# ESP_Uart-V2.net
KiCad netlist of a schematic drawn in EAGLE
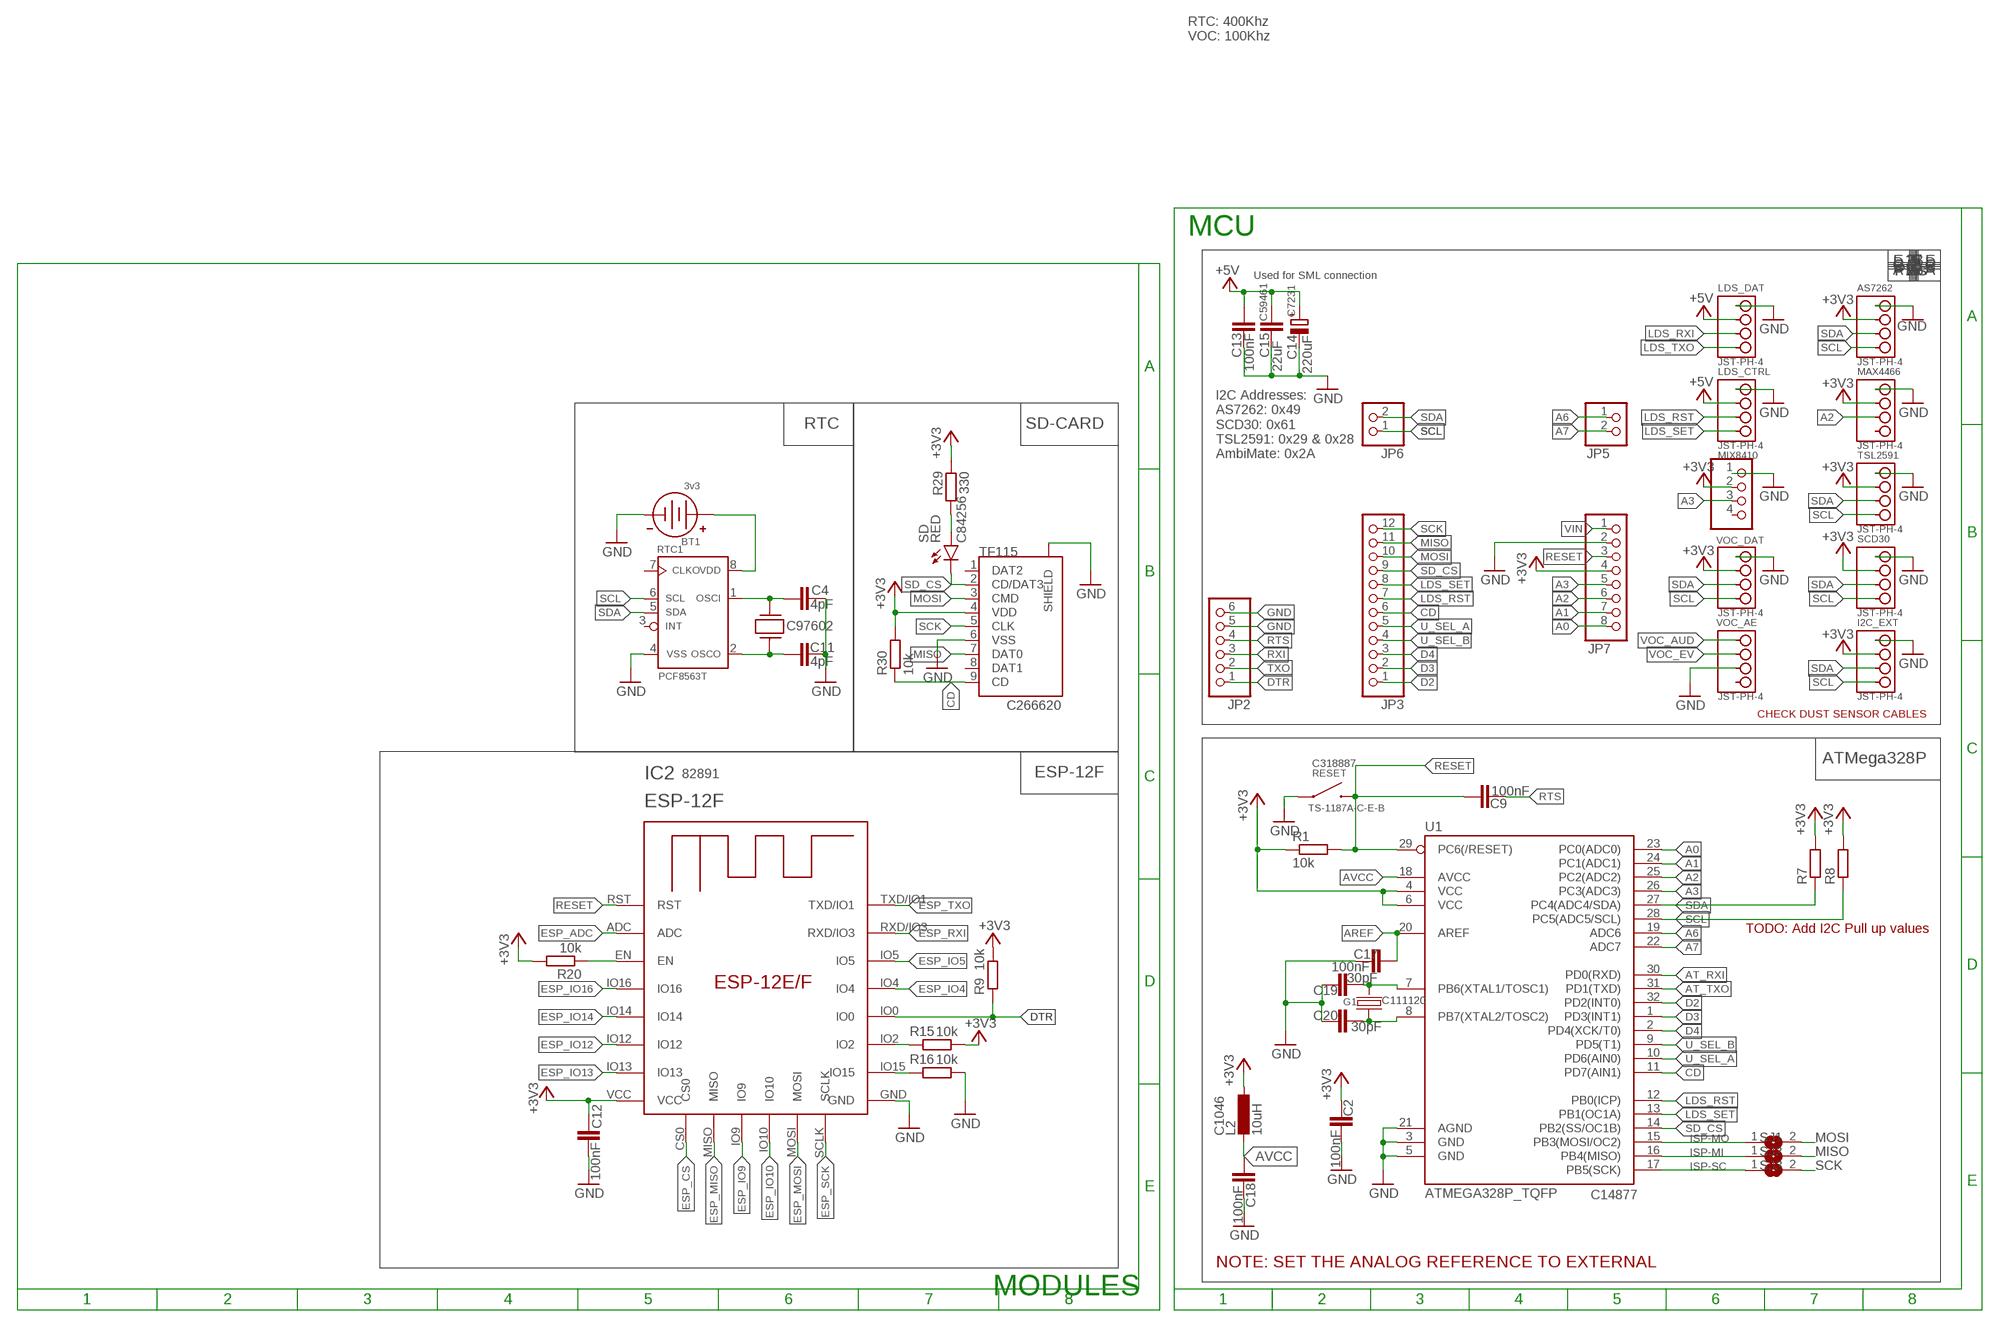
[diagram p0: schematic, sheet 1, part 1 of 2]
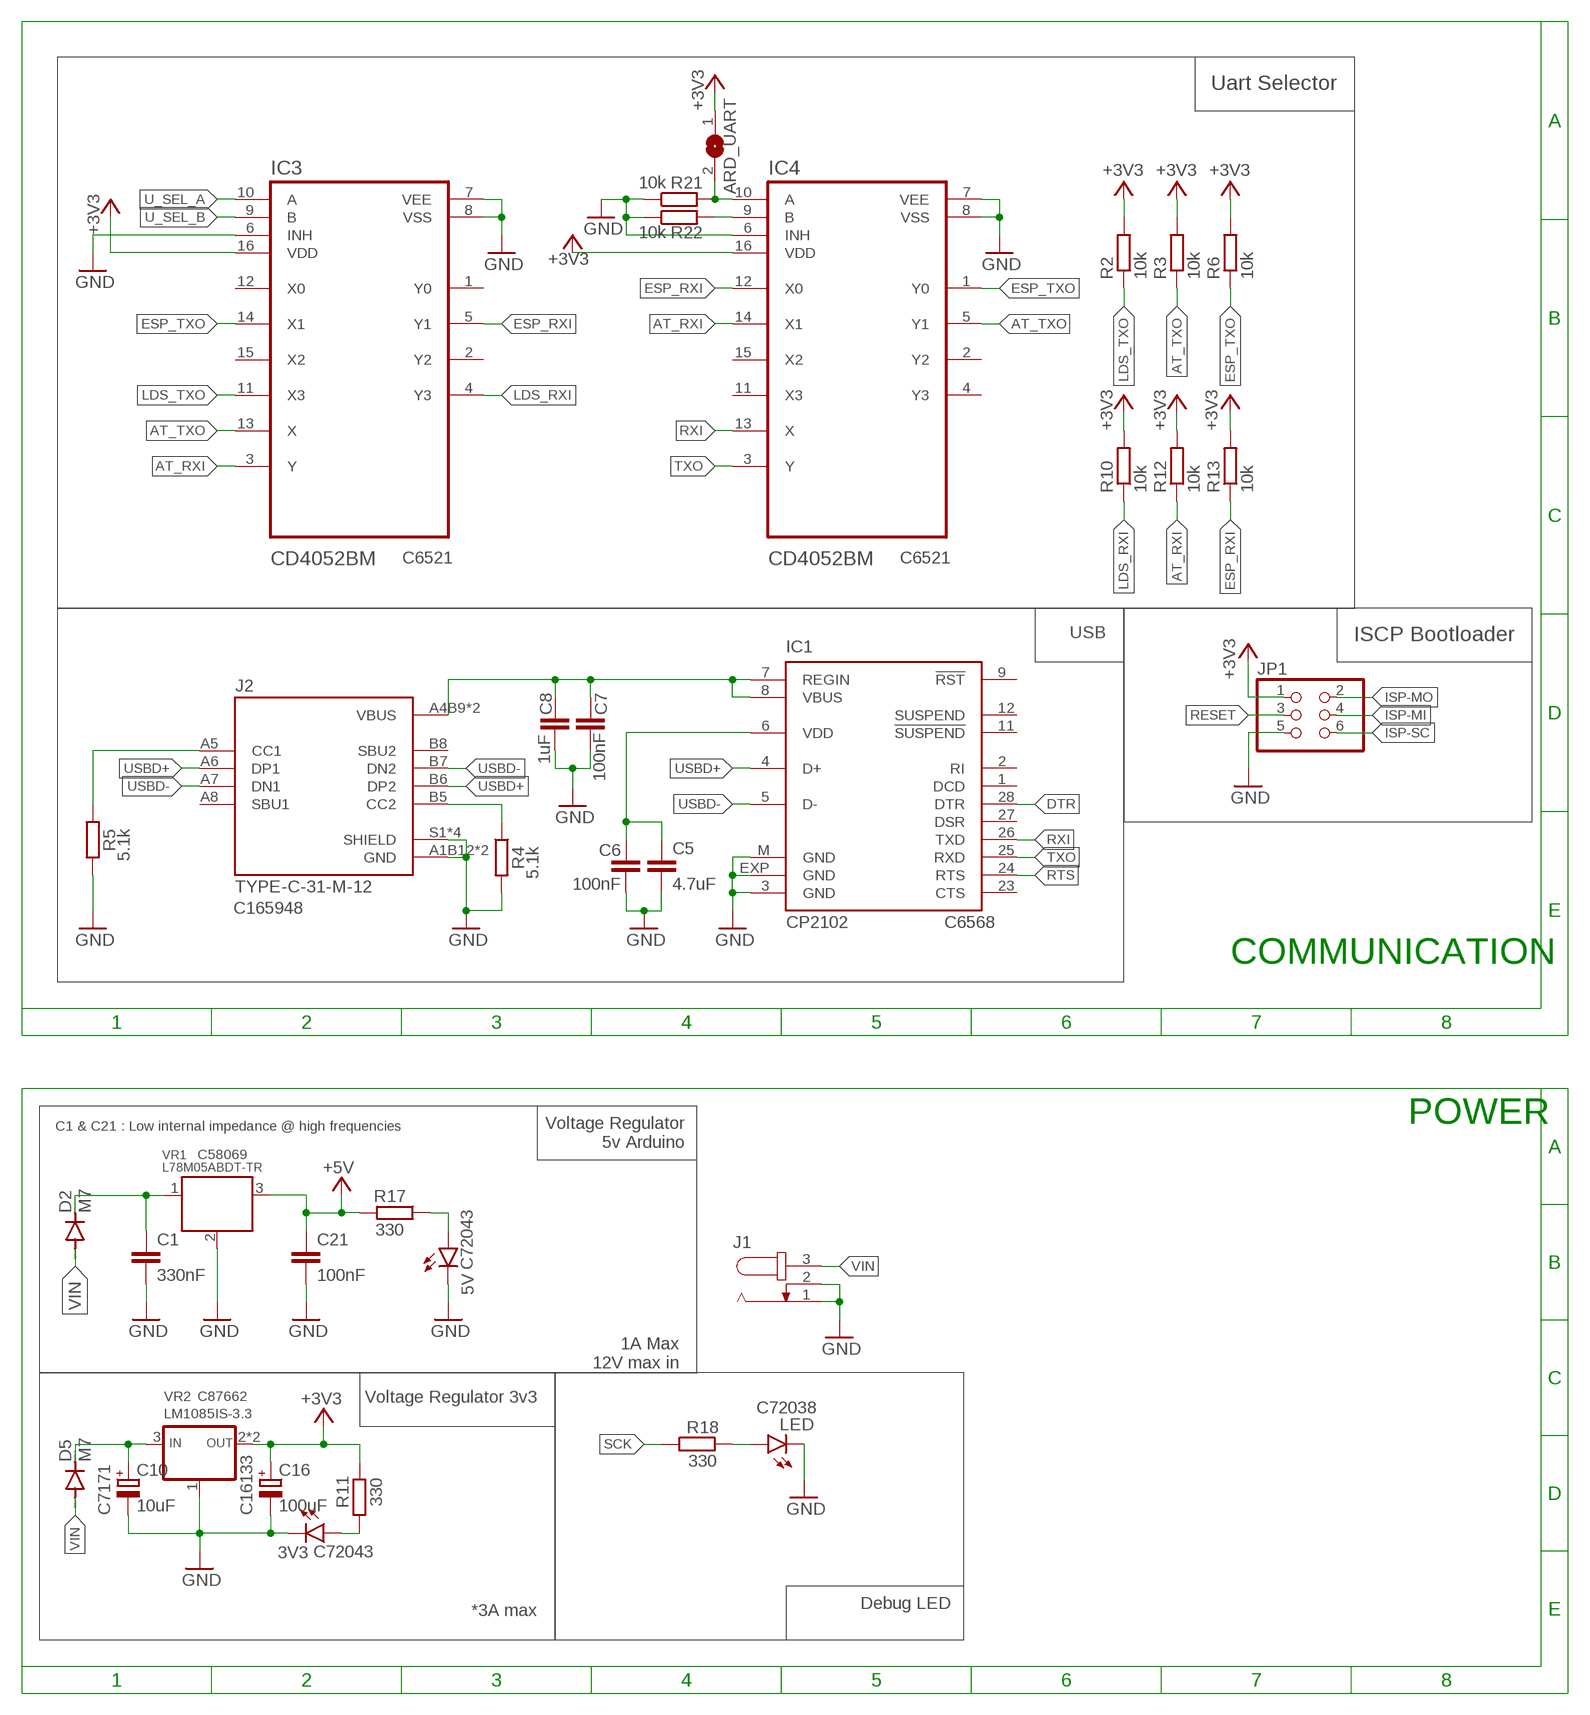
[diagram p1: schematic, sheet 1, part 2 of 2]

(export (version "E")
  (design (tool "Eeschema 10.0.6"))
  (components
    (comp (ref "3V3")
      (value "C72043")
      (footprint "eagle-import:CHIPLED_0603")
      (fields (field (name "PTNR") "C72043"))
      (libsource (lib "eagle-import") (part "LEDCHIPLED_0603"))
    )
    (comp (ref "5V")
      (value "C72043")
      (footprint "eagle-import:CHIPLED_0603")
      (fields (field (name "PTNR") "C72043"))
      (libsource (lib "eagle-import") (part "LEDCHIPLED_0603"))
    )
    (comp (ref "ARD_UART")
      (value "SJ")
      (footprint "eagle-import:SJ")
      (libsource (lib "eagle-import") (part "SJ"))
    )
    (comp (ref "AS7262")
      (value "JST-PH-4")
      (footprint "eagle-import:JST-PH-4")
      (libsource (lib "eagle-import") (part "JST-PH-4"))
    )
    (comp (ref "BT1")
      (value "3v3")
      (footprint "eagle-import:CH29-2032LF")
      (libsource (lib "eagle-import") (part "CH29-2032LF"))
    )
    (comp (ref "C1")
      (value "330nF")
      (footprint "eagle-import:C0805")
      (libsource (lib "eagle-import") (part "C-EUC0805"))
    )
    (comp (ref "C2")
      (value "100nF")
      (footprint "eagle-import:C0402")
      (libsource (lib "eagle-import") (part "C-EUC0402"))
    )
    (comp (ref "C4")
      (value "4pF")
      (footprint "eagle-import:C0402")
      (libsource (lib "eagle-import") (part "C-EUC0402"))
    )
    (comp (ref "C5")
      (value "4.7uF")
      (footprint "eagle-import:C0402")
      (libsource (lib "eagle-import") (part "C-EUC0402"))
    )
    (comp (ref "C6")
      (value "100nF")
      (footprint "eagle-import:C0402")
      (libsource (lib "eagle-import") (part "C-EUC0402"))
    )
    (comp (ref "C7")
      (value "100nF")
      (footprint "eagle-import:C0402")
      (libsource (lib "eagle-import") (part "C-EUC0402"))
    )
    (comp (ref "C8")
      (value "1uF")
      (footprint "eagle-import:C0402")
      (libsource (lib "eagle-import") (part "C-EUC0402"))
    )
    (comp (ref "C9")
      (value "100nF")
      (footprint "eagle-import:C0402")
      (libsource (lib "eagle-import") (part "C-EUC0402"))
    )
    (comp (ref "C10")
      (value "10uF")
      (footprint "eagle-import:A_3216-18R")
      (fields (field (name "PTRNR") "C7171"))
      (libsource (lib "eagle-import") (part "CPOL-EUA/3216-18R"))
    )
    (comp (ref "C11")
      (value "4pF")
      (footprint "eagle-import:C0402")
      (libsource (lib "eagle-import") (part "C-EUC0402"))
    )
    (comp (ref "C12")
      (value "100nF")
      (footprint "eagle-import:C0402")
      (libsource (lib "eagle-import") (part "C-EUC0402"))
    )
    (comp (ref "C13")
      (value "100nF")
      (footprint "eagle-import:C0402")
      (libsource (lib "eagle-import") (part "C-EUC0402"))
    )
    (comp (ref "C14")
      (value "220uF")
      (footprint "eagle-import:A_3216-18R")
      (fields (field (name "PTRNR") "C7231"))
      (libsource (lib "eagle-import") (part "CPOL-EUA/3216-18R"))
    )
    (comp (ref "C15")
      (value "22uF")
      (footprint "eagle-import:C0603")
      (fields (field (name "PTRNR") "C59461"))
      (libsource (lib "eagle-import") (part "C-EUC0603"))
    )
    (comp (ref "C16")
      (value "100uF")
      (footprint "eagle-import:B_3528-21W")
      (fields (field (name "PTRNR") "C16133"))
      (libsource (lib "eagle-import") (part "CPOL-EUB/3528-21W"))
    )
    (comp (ref "C17")
      (value "100nF")
      (footprint "eagle-import:C0402")
      (libsource (lib "eagle-import") (part "C-EUC0402"))
    )
    (comp (ref "C18")
      (value "100nF")
      (footprint "eagle-import:C0402")
      (libsource (lib "eagle-import") (part "C-EUC0402"))
    )
    (comp (ref "C19")
      (value "30pF")
      (footprint "eagle-import:C0402")
      (libsource (lib "eagle-import") (part "C-EUC0402"))
    )
    (comp (ref "C20")
      (value "30pF")
      (footprint "eagle-import:C0402")
      (libsource (lib "eagle-import") (part "C-EUC0402"))
    )
    (comp (ref "C21")
      (value "100nF")
      (footprint "eagle-import:C0402")
      (libsource (lib "eagle-import") (part "C-EUC0402"))
    )
    (comp (ref "D2")
      (value "M7")
      (footprint "eagle-import:DO-214AC")
      (libsource (lib "eagle-import") (part "M7DO-214AC"))
    )
    (comp (ref "D5")
      (value "M7")
      (footprint "eagle-import:DO-214AC")
      (libsource (lib "eagle-import") (part "M7DO-214AC"))
    )
    (comp (ref "G1")
      (value "8Mhz")
      (footprint "eagle-import:7A08000008")
      (fields (field (name "PTRNR") "C111120"))
      (libsource (lib "eagle-import") (part "7A08000008"))
    )
    (comp (ref "G2")
      (value "32.768KHZ")
      (footprint "eagle-import:32.768KHZ")
      (fields (field (name "PTRNR") "C97602"))
      (libsource (lib "eagle-import") (part "32.768KHZ"))
    )
    (comp (ref "I2C_EXT")
      (value "JST-PH-4")
      (footprint "eagle-import:JST-PH-4")
      (libsource (lib "eagle-import") (part "JST-PH-4"))
    )
    (comp (ref "IC1")
      (value "CP2102")
      (footprint "eagle-import:MLP28")
      (fields
        (field (name "MF") "FARNELL")
        (field (name "MPN") "CP2102-GM")
        (field (name "PTRNR") "C6568")
        (field (name "PTRNR_1") "C6568")
      )
      (libsource (lib "eagle-import") (part "CP2102"))
    )
    (comp (ref "IC2")
      (value "ESP-12F")
      (footprint "eagle-import:ESP-12E")
      (fields (field (name "PTRNR") "82891"))
      (libsource (lib "eagle-import") (part "ESP-12F"))
    )
    (comp (ref "IC3")
      (value "CD4052BM")
      (footprint "eagle-import:SOIC127P600X175-16N")
      (fields
        (field (name "MF") "Texas Instruments")
        (field (name "PTRNR") "C6521")
        (field (name "PTRNR_1") "C6521")
      )
      (libsource (lib "eagle-import") (part "CD4052BM"))
    )
    (comp (ref "IC4")
      (value "CD4052BM")
      (footprint "eagle-import:SOIC127P600X175-16N")
      (fields
        (field (name "MF") "Texas Instruments")
        (field (name "PTRNR") "C6521")
        (field (name "PTRNR_1") "C6521")
      )
      (libsource (lib "eagle-import") (part "CD4052BM"))
    )
    (comp (ref "J1")
      (value "JACK-PLUG1")
      (footprint "eagle-import:SPC4078")
      (libsource (lib "eagle-import") (part "JACK-PLUG1"))
    )
    (comp (ref "J2")
      (value "TYPE-C-31-M-12")
      (footprint "eagle-import:HRO_TYPE-C-31-M-12")
      (fields
        (field (name "MF") "HRO Electronics Co., Ltd.")
        (field (name "PTRNR") "C165948")
        (field (name "PTRNR_1") "C165948")
      )
      (libsource (lib "eagle-import") (part "TYPE-C-31-M-12"))
    )
    (comp (ref "JP1")
      (value "PINHD-2X3")
      (footprint "eagle-import:2X03")
      (libsource (lib "eagle-import") (part "PINHD-2X3"))
    )
    (comp (ref "JP2")
      (value "PINHD-1X6/90")
      (footprint "eagle-import:1X06_90")
      (libsource (lib "eagle-import") (part "PINHD-1X6/90"))
    )
    (comp (ref "JP3")
      (value "PINHD-1X12")
      (footprint "eagle-import:1X12")
      (libsource (lib "eagle-import") (part "PINHD-1X12"))
    )
    (comp (ref "JP5")
      (value "PINHD-1X2/90")
      (footprint "eagle-import:1X02_90")
      (libsource (lib "eagle-import") (part "PINHD-1X2/90"))
    )
    (comp (ref "JP6")
      (value "PINHD-1X2/90")
      (footprint "eagle-import:1X02_90")
      (libsource (lib "eagle-import") (part "PINHD-1X2/90"))
    )
    (comp (ref "JP7")
      (value "PINHD-1X8")
      (footprint "eagle-import:1X08")
      (libsource (lib "eagle-import") (part "PINHD-1X8"))
    )
    (comp (ref "L2")
      (value "10uH")
      (footprint "eagle-import:L2012C")
      (fields (field (name "PRTNR") "C1046"))
      (libsource (lib "eagle-import") (part "L-EUL2012C"))
    )
    (comp (ref "LDS_CTRL")
      (value "JST-PH-4")
      (footprint "eagle-import:JST-PH-4")
      (libsource (lib "eagle-import") (part "JST-PH-4"))
    )
    (comp (ref "LDS_DAT")
      (value "JST-PH-4")
      (footprint "eagle-import:JST-PH-4")
      (libsource (lib "eagle-import") (part "JST-PH-4"))
    )
    (comp (ref "LED")
      (value "YELLOW")
      (footprint "eagle-import:CHIPLED_0603")
      (fields (field (name "PTRNR") "C72038"))
      (libsource (lib "eagle-import") (part "LEDCHIPLED_0603"))
    )
    (comp (ref "MAX4466")
      (value "JST-PH-4")
      (footprint "eagle-import:JST-PH-4")
      (libsource (lib "eagle-import") (part "JST-PH-4"))
    )
    (comp (ref "MIX8410")
      (value "PINHD-1X4")
      (footprint "eagle-import:1X04")
      (libsource (lib "eagle-import") (part "PINHD-1X4"))
    )
    (comp (ref "R1")
      (value "10k")
      (footprint "eagle-import:R0402")
      (libsource (lib "eagle-import") (part "R-EU_R0402"))
    )
    (comp (ref "R2")
      (value "10k")
      (footprint "eagle-import:R0402")
      (libsource (lib "eagle-import") (part "R-EU_R0402"))
    )
    (comp (ref "R3")
      (value "10k")
      (footprint "eagle-import:R0402")
      (libsource (lib "eagle-import") (part "R-EU_R0402"))
    )
    (comp (ref "R4")
      (value "5.1k")
      (footprint "eagle-import:R0402")
      (libsource (lib "eagle-import") (part "R-EU_R0402"))
    )
    (comp (ref "R5")
      (value "5.1k")
      (footprint "eagle-import:R0402")
      (libsource (lib "eagle-import") (part "R-EU_R0402"))
    )
    (comp (ref "R6")
      (value "10k")
      (footprint "eagle-import:R0402")
      (libsource (lib "eagle-import") (part "R-EU_R0402"))
    )
    (comp (ref "R7")
      (value "R-EU_R0402")
      (footprint "eagle-import:R0402")
      (libsource (lib "eagle-import") (part "R-EU_R0402"))
    )
    (comp (ref "R8")
      (value "R-EU_R0402")
      (footprint "eagle-import:R0402")
      (libsource (lib "eagle-import") (part "R-EU_R0402"))
    )
    (comp (ref "R9")
      (value "10k")
      (footprint "eagle-import:R0402")
      (libsource (lib "eagle-import") (part "R-EU_R0402"))
    )
    (comp (ref "R10")
      (value "10k")
      (footprint "eagle-import:R0402")
      (libsource (lib "eagle-import") (part "R-EU_R0402"))
    )
    (comp (ref "R11")
      (value "330")
      (footprint "eagle-import:M0805")
      (libsource (lib "eagle-import") (part "R-EU_M0805"))
    )
    (comp (ref "R12")
      (value "10k")
      (footprint "eagle-import:R0402")
      (libsource (lib "eagle-import") (part "R-EU_R0402"))
    )
    (comp (ref "R13")
      (value "10k")
      (footprint "eagle-import:R0402")
      (libsource (lib "eagle-import") (part "R-EU_R0402"))
    )
    (comp (ref "R15")
      (value "10k")
      (footprint "eagle-import:R0402")
      (libsource (lib "eagle-import") (part "R-EU_R0402"))
    )
    (comp (ref "R16")
      (value "10k")
      (footprint "eagle-import:R0402")
      (libsource (lib "eagle-import") (part "R-EU_R0402"))
    )
    (comp (ref "R17")
      (value "330")
      (footprint "eagle-import:M0805")
      (libsource (lib "eagle-import") (part "R-EU_M0805"))
    )
    (comp (ref "R18")
      (value "330")
      (footprint "eagle-import:M0805")
      (libsource (lib "eagle-import") (part "R-EU_M0805"))
    )
    (comp (ref "R20")
      (value "10k")
      (footprint "eagle-import:R0402")
      (libsource (lib "eagle-import") (part "R-EU_R0402"))
    )
    (comp (ref "R21")
      (value "10k")
      (footprint "eagle-import:R0402")
      (libsource (lib "eagle-import") (part "R-EU_R0402"))
    )
    (comp (ref "R22")
      (value "10k")
      (footprint "eagle-import:R0402")
      (libsource (lib "eagle-import") (part "R-EU_R0402"))
    )
    (comp (ref "R29")
      (value "330")
      (footprint "eagle-import:R0402")
      (libsource (lib "eagle-import") (part "R-EU_R0402"))
    )
    (comp (ref "R30")
      (value "10k")
      (footprint "eagle-import:R0402")
      (libsource (lib "eagle-import") (part "R-EU_R0402"))
    )
    (comp (ref "RESET")
      (value "TS-1187A-C-E-B")
      (footprint "eagle-import:TS-1187A-C-E-B")
      (fields (field (name "PRTNR") "C318887") (field (name "PRTNR_1") "C318887"))
      (libsource (lib "eagle-import") (part "TS-1187A-C-E-B"))
    )
    (comp (ref "RTC1")
      (value "PCF8563T")
      (footprint "eagle-import:SOIC8")
      (libsource (lib "eagle-import") (part "PCF8563T"))
    )
    (comp (ref "SCD30")
      (value "JST-PH-4")
      (footprint "eagle-import:JST-PH-4")
      (libsource (lib "eagle-import") (part "JST-PH-4"))
    )
    (comp (ref "SD")
      (value "RED")
      (footprint "eagle-import:CHIPLED_0805")
      (fields (field (name "PTRNR") "C84256"))
      (libsource (lib "eagle-import") (part "LEDCHIPLED_0805"))
    )
    (comp (ref "SJ1") (value "SJ") (footprint "eagle-import:SJ") (libsource (lib "eagle-import") (part "SJ")))
    (comp (ref "SJ2") (value "SJ") (footprint "eagle-import:SJ") (libsource (lib "eagle-import") (part "SJ")))
    (comp (ref "SJ3") (value "SJ") (footprint "eagle-import:SJ") (libsource (lib "eagle-import") (part "SJ")))
    (comp (ref "TF115")
      (value "TF-115")
      (footprint "eagle-import:TF-115")
      (fields (field (name "PTRNR") "C266620"))
      (libsource (lib "eagle-import") (part "TF-115"))
    )
    (comp (ref "TSL2591")
      (value "JST-PH-4")
      (footprint "eagle-import:JST-PH-4")
      (libsource (lib "eagle-import") (part "JST-PH-4"))
    )
    (comp (ref "U1")
      (value "ATMEGA328P_TQFP")
      (footprint "eagle-import:TQFP32-08")
      (fields (field (name "PTRNR") "C14877"))
      (libsource (lib "eagle-import") (part "ATMEGA328P_TQFP"))
    )
    (comp (ref "VOC_AE")
      (value "JST-PH-4")
      (footprint "eagle-import:JST-PH-4")
      (libsource (lib "eagle-import") (part "JST-PH-4"))
    )
    (comp (ref "VOC_DAT")
      (value "JST-PH-4")
      (footprint "eagle-import:JST-PH-4")
      (libsource (lib "eagle-import") (part "JST-PH-4"))
    )
    (comp (ref "VR1")
      (value "L78M05ABDT-TR")
      (footprint "eagle-import:DPAK")
      (fields (field (name "PTRNR") "C58069"))
      (libsource (lib "eagle-import") (part "L78M05ABDT-TR"))
    )
    (comp (ref "VR2")
      (value "LM1085IS-3.3")
      (footprint "eagle-import:TO263-3")
      (fields (field (name "PTRNR") "C87662") (field (name "PTRNR_1") "C87662"))
      (libsource (lib "eagle-import") (part "LM1085IS-3.3"))
    )
  )
  (nets
    (net (code "1") (name "+3V3") (class "Default")
      (node (ref "ARD_UART") (pin "1") (pinfunction "1_1") (pintype "passive"))
      (node (ref "AS7262") (pin "P2") (pinfunction "2_P2") (pintype "bidirectional"))
      (node (ref "C12") (pin "1") (pinfunction "1_1") (pintype "passive"))
      (node (ref "C16") (pin "+") (pinfunction "+_+") (pintype "passive"))
      (node (ref "C2") (pin "2") (pinfunction "2_2") (pintype "passive"))
      (node (ref "I2C_EXT") (pin "P2") (pinfunction "2_P2") (pintype "bidirectional"))
      (node (ref "IC2") (pin "VCC") (pinfunction "VCC_VCC") (pintype "power_in"))
      (node (ref "IC3") (pin "16") (pinfunction "VDD_16") (pintype "input"))
      (node (ref "IC4") (pin "16") (pinfunction "VDD_16") (pintype "input"))
      (node (ref "JP1") (pin "1") (pinfunction "1_1") (pintype "passive"))
      (node (ref "JP7") (pin "4") (pinfunction "4_4") (pintype "passive"))
      (node (ref "L2") (pin "1") (pinfunction "1_1") (pintype "passive"))
      (node (ref "MAX4466") (pin "P2") (pinfunction "2_P2") (pintype "bidirectional"))
      (node (ref "MIX8410") (pin "2") (pinfunction "2_2") (pintype "passive"))
      (node (ref "R1") (pin "1") (pinfunction "1_1") (pintype "passive"))
      (node (ref "R10") (pin "2") (pinfunction "2_2") (pintype "passive"))
      (node (ref "R11") (pin "2") (pinfunction "2_2") (pintype "passive"))
      (node (ref "R12") (pin "2") (pinfunction "2_2") (pintype "passive"))
      (node (ref "R13") (pin "2") (pinfunction "2_2") (pintype "passive"))
      (node (ref "R15") (pin "1") (pinfunction "1_1") (pintype "passive"))
      (node (ref "R2") (pin "2") (pinfunction "2_2") (pintype "passive"))
      (node (ref "R20") (pin "2") (pinfunction "2_2") (pintype "passive"))
      (node (ref "R29") (pin "2") (pinfunction "2_2") (pintype "passive"))
      (node (ref "R3") (pin "2") (pinfunction "2_2") (pintype "passive"))
      (node (ref "R30") (pin "2") (pinfunction "2_2") (pintype "passive"))
      (node (ref "R6") (pin "2") (pinfunction "2_2") (pintype "passive"))
      (node (ref "R7") (pin "2") (pinfunction "2_2") (pintype "passive"))
      (node (ref "R8") (pin "2") (pinfunction "2_2") (pintype "passive"))
      (node (ref "R9") (pin "1") (pinfunction "1_1") (pintype "passive"))
      (node (ref "SCD30") (pin "P2") (pinfunction "2_P2") (pintype "bidirectional"))
      (node (ref "TF115") (pin "4") (pinfunction "VDD_4") (pintype "bidirectional"))
      (node (ref "TSL2591") (pin "P2") (pinfunction "2_P2") (pintype "bidirectional"))
      (node (ref "U1") (pin "4") (pinfunction "VCC_4") (pintype "bidirectional"))
      (node (ref "U1") (pin "6") (pinfunction "VCC_6") (pintype "bidirectional"))
      (node (ref "VOC_DAT") (pin "P2") (pinfunction "2_P2") (pintype "bidirectional"))
      (node (ref "VR2") (pin "2") (pinfunction "OUT_2") (pintype "output"))
      (node (ref "VR2") (pin "TAB") (pinfunction "OUT_TAB") (pintype "output"))
    )
    (net (code "2") (name "+5V") (class "Default")
      (node (ref "C13") (pin "1") (pinfunction "1_1") (pintype "passive"))
      (node (ref "C14") (pin "+") (pinfunction "+_+") (pintype "passive"))
      (node (ref "C15") (pin "1") (pinfunction "1_1") (pintype "passive"))
      (node (ref "C21") (pin "1") (pinfunction "1_1") (pintype "passive"))
      (node (ref "LDS_CTRL") (pin "P2") (pinfunction "2_P2") (pintype "bidirectional"))
      (node (ref "LDS_DAT") (pin "P2") (pinfunction "2_P2") (pintype "bidirectional"))
      (node (ref "R17") (pin "2") (pinfunction "2_2") (pintype "passive"))
      (node (ref "VR1") (pin "3") (pinfunction "VO_3") (pintype "output"))
    )
    (net (code "3") (name "A0") (class "Default")
      (node (ref "JP7") (pin "8") (pinfunction "8_8") (pintype "passive"))
      (node (ref "U1") (pin "23") (pinfunction "PC0(ADC0)_23") (pintype "bidirectional"))
    )
    (net (code "4") (name "A1") (class "Default")
      (node (ref "JP7") (pin "7") (pinfunction "7_7") (pintype "passive"))
      (node (ref "U1") (pin "24") (pinfunction "PC1(ADC1)_24") (pintype "bidirectional"))
    )
    (net (code "5") (name "A2") (class "Default")
      (node (ref "JP7") (pin "6") (pinfunction "6_6") (pintype "passive"))
      (node (ref "MAX4466") (pin "P3") (pinfunction "3_P3") (pintype "bidirectional"))
      (node (ref "U1") (pin "25") (pinfunction "PC2(ADC2)_25") (pintype "bidirectional"))
    )
    (net (code "6") (name "A3") (class "Default")
      (node (ref "JP7") (pin "5") (pinfunction "5_5") (pintype "passive"))
      (node (ref "MIX8410") (pin "3") (pinfunction "3_3") (pintype "passive"))
      (node (ref "U1") (pin "26") (pinfunction "PC3(ADC3)_26") (pintype "bidirectional"))
    )
    (net (code "7") (name "A6") (class "Default")
      (node (ref "JP5") (pin "1") (pinfunction "1_1") (pintype "passive"))
      (node (ref "U1") (pin "19") (pinfunction "ADC6_19") (pintype "bidirectional"))
    )
    (net (code "8") (name "A7") (class "Default")
      (node (ref "JP5") (pin "2") (pinfunction "2_2") (pintype "passive"))
      (node (ref "U1") (pin "22") (pinfunction "ADC7_22") (pintype "bidirectional"))
    )
    (net (code "9") (name "AREF") (class "Default")
      (node (ref "C17") (pin "1") (pinfunction "1_1") (pintype "passive"))
      (node (ref "U1") (pin "20") (pinfunction "AREF_20") (pintype "bidirectional"))
    )
    (net (code "10") (name "AT_RXI") (class "Default")
      (node (ref "IC3") (pin "3") (pinfunction "Y_3") (pintype "bidirectional"))
      (node (ref "IC4") (pin "14") (pinfunction "X1_14") (pintype "bidirectional"))
      (node (ref "R12") (pin "1") (pinfunction "1_1") (pintype "passive"))
      (node (ref "U1") (pin "30") (pinfunction "PD0(RXD)_30") (pintype "bidirectional"))
    )
    (net (code "11") (name "AT_TXO") (class "Default")
      (node (ref "IC3") (pin "13") (pinfunction "X_13") (pintype "bidirectional"))
      (node (ref "IC4") (pin "5") (pinfunction "Y1_5") (pintype "bidirectional"))
      (node (ref "R3") (pin "1") (pinfunction "1_1") (pintype "passive"))
      (node (ref "U1") (pin "31") (pinfunction "PD1(TXD)_31") (pintype "bidirectional"))
    )
    (net (code "12") (name "AVCC") (class "Default")
      (node (ref "C18") (pin "2") (pinfunction "2_2") (pintype "passive"))
      (node (ref "L2") (pin "2") (pinfunction "2_2") (pintype "passive"))
      (node (ref "U1") (pin "18") (pinfunction "AVCC_18") (pintype "bidirectional"))
    )
    (net (code "13") (name "CD") (class "Default")
      (node (ref "JP3") (pin "6") (pinfunction "6_6") (pintype "passive"))
      (node (ref "R30") (pin "1") (pinfunction "1_1") (pintype "passive"))
      (node (ref "TF115") (pin "9") (pinfunction "CD_9") (pintype "bidirectional"))
      (node (ref "U1") (pin "11") (pinfunction "PD7(AIN1)_11") (pintype "bidirectional"))
    )
    (net (code "14") (name "D2") (class "Default")
      (node (ref "JP3") (pin "1") (pinfunction "1_1") (pintype "passive"))
      (node (ref "U1") (pin "32") (pinfunction "PD2(INT0)_32") (pintype "bidirectional"))
    )
    (net (code "15") (name "D3") (class "Default")
      (node (ref "JP3") (pin "2") (pinfunction "2_2") (pintype "passive"))
      (node (ref "U1") (pin "1") (pinfunction "PD3(INT1)_1") (pintype "bidirectional"))
    )
    (net (code "16") (name "D4") (class "Default")
      (node (ref "JP3") (pin "3") (pinfunction "3_3") (pintype "passive"))
      (node (ref "U1") (pin "2") (pinfunction "PD4(XCK/T0)_2") (pintype "bidirectional"))
    )
    (net (code "17") (name "DTR") (class "Default")
      (node (ref "IC1") (pin "28") (pinfunction "DTR_28") (pintype "output"))
      (node (ref "IC2") (pin "IO0") (pinfunction "IO0_IO0") (pintype "bidirectional"))
      (node (ref "JP2") (pin "1") (pinfunction "1_1") (pintype "passive"))
      (node (ref "R9") (pin "2") (pinfunction "2_2") (pintype "passive"))
    )
    (net (code "18") (name "ESP_ADC") (class "Default")
      (node (ref "IC2") (pin "ADC") (pinfunction "ADC_ADC") (pintype "bidirectional"))
    )
    (net (code "19") (name "ESP_CS") (class "Default")
      (node (ref "IC2") (pin "CS0") (pinfunction "CS0_CS0") (pintype "bidirectional"))
    )
    (net (code "20") (name "ESP_IO4") (class "Default")
      (node (ref "IC2") (pin "IO4") (pinfunction "IO4_IO4") (pintype "bidirectional"))
    )
    (net (code "21") (name "ESP_IO5") (class "Default")
      (node (ref "IC2") (pin "IO5") (pinfunction "IO5_IO5") (pintype "bidirectional"))
    )
    (net (code "22") (name "ESP_IO9") (class "Default")
      (node (ref "IC2") (pin "IO9") (pinfunction "IO9_IO9") (pintype "bidirectional"))
    )
    (net (code "23") (name "ESP_IO10") (class "Default")
      (node (ref "IC2") (pin "IO10") (pinfunction "IO10_IO10") (pintype "bidirectional"))
    )
    (net (code "24") (name "ESP_IO12") (class "Default")
      (node (ref "IC2") (pin "IO12") (pinfunction "IO12_IO12") (pintype "bidirectional"))
    )
    (net (code "25") (name "ESP_IO13") (class "Default")
      (node (ref "IC2") (pin "IO13") (pinfunction "IO13_IO13") (pintype "bidirectional"))
    )
    (net (code "26") (name "ESP_IO14") (class "Default")
      (node (ref "IC2") (pin "IO14") (pinfunction "IO14_IO14") (pintype "bidirectional"))
    )
    (net (code "27") (name "ESP_IO16") (class "Default")
      (node (ref "IC2") (pin "IO16") (pinfunction "IO16_IO16") (pintype "bidirectional"))
    )
    (net (code "28") (name "ESP_MISO") (class "Default")
      (node (ref "IC2") (pin "MISO") (pinfunction "MISO_MISO") (pintype "bidirectional"))
    )
    (net (code "29") (name "ESP_MOSI") (class "Default")
      (node (ref "IC2") (pin "MOSI") (pinfunction "MOSI_MOSI") (pintype "bidirectional"))
    )
    (net (code "30") (name "ESP_RXI") (class "Default")
      (node (ref "IC2") (pin "RXD/IO3") (pinfunction "RXD/IO3_RXD/IO3") (pintype "bidirectional"))
      (node (ref "IC3") (pin "5") (pinfunction "Y1_5") (pintype "bidirectional"))
      (node (ref "IC4") (pin "12") (pinfunction "X0_12") (pintype "bidirectional"))
      (node (ref "R13") (pin "1") (pinfunction "1_1") (pintype "passive"))
    )
    (net (code "31") (name "ESP_SCK") (class "Default")
      (node (ref "IC2") (pin "SCLK") (pinfunction "SCLK_SCLK") (pintype "bidirectional"))
    )
    (net (code "32") (name "ESP_TXO") (class "Default")
      (node (ref "IC2") (pin "TXD/IO1") (pinfunction "TXD/IO1_TXD/IO1") (pintype "bidirectional"))
      (node (ref "IC3") (pin "14") (pinfunction "X1_14") (pintype "bidirectional"))
      (node (ref "IC4") (pin "1") (pinfunction "Y0_1") (pintype "bidirectional"))
      (node (ref "R6") (pin "1") (pinfunction "1_1") (pintype "passive"))
    )
    (net (code "33") (name "GND") (class "Default")
      (node (ref "3V3") (pin "C") (pinfunction "C_C") (pintype "passive"))
      (node (ref "5V") (pin "C") (pinfunction "C_C") (pintype "passive"))
      (node (ref "AS7262") (pin "P1") (pinfunction "1_P1") (pintype "bidirectional"))
      (node (ref "BT1") (pin "GND") (pinfunction "GND_GND") (pintype "power_in"))
      (node (ref "C1") (pin "2") (pinfunction "2_2") (pintype "passive"))
      (node (ref "C10") (pin "-") (pinfunction "-_-") (pintype "passive"))
      (node (ref "C11") (pin "2") (pinfunction "2_2") (pintype "passive"))
      (node (ref "C12") (pin "2") (pinfunction "2_2") (pintype "passive"))
      (node (ref "C13") (pin "2") (pinfunction "2_2") (pintype "passive"))
      (node (ref "C14") (pin "-") (pinfunction "-_-") (pintype "passive"))
      (node (ref "C15") (pin "2") (pinfunction "2_2") (pintype "passive"))
      (node (ref "C16") (pin "-") (pinfunction "-_-") (pintype "passive"))
      (node (ref "C17") (pin "2") (pinfunction "2_2") (pintype "passive"))
      (node (ref "C18") (pin "1") (pinfunction "1_1") (pintype "passive"))
      (node (ref "C19") (pin "2") (pinfunction "2_2") (pintype "passive"))
      (node (ref "C2") (pin "1") (pinfunction "1_1") (pintype "passive"))
      (node (ref "C20") (pin "2") (pinfunction "2_2") (pintype "passive"))
      (node (ref "C21") (pin "2") (pinfunction "2_2") (pintype "passive"))
      (node (ref "C4") (pin "2") (pinfunction "2_2") (pintype "passive"))
      (node (ref "C5") (pin "2") (pinfunction "2_2") (pintype "passive"))
      (node (ref "C6") (pin "2") (pinfunction "2_2") (pintype "passive"))
      (node (ref "C7") (pin "2") (pinfunction "2_2") (pintype "passive"))
      (node (ref "C8") (pin "2") (pinfunction "2_2") (pintype "passive"))
      (node (ref "I2C_EXT") (pin "P1") (pinfunction "1_P1") (pintype "bidirectional"))
      (node (ref "IC1") (pin "3") (pinfunction "GND_3") (pintype "power_in"))
      (node (ref "IC1") (pin "EXP") (pinfunction "GND_EXP") (pintype "power_in"))
      (node (ref "IC1") (pin "M") (pinfunction "GND_M") (pintype "power_in"))
      (node (ref "IC2") (pin "GND") (pinfunction "GND_GND") (pintype "power_in"))
      (node (ref "IC3") (pin "6") (pinfunction "INH_6") (pintype "input"))
      (node (ref "IC3") (pin "7") (pinfunction "VEE_7") (pintype "power_in"))
      (node (ref "IC3") (pin "8") (pinfunction "VSS_8") (pintype "power_in"))
      (node (ref "IC4") (pin "6") (pinfunction "INH_6") (pintype "input"))
      (node (ref "IC4") (pin "7") (pinfunction "VEE_7") (pintype "power_in"))
      (node (ref "IC4") (pin "8") (pinfunction "VSS_8") (pintype "power_in"))
      (node (ref "J1") (pin "1") (pinfunction "1_1") (pintype "passive"))
      (node (ref "J1") (pin "2") (pinfunction "2_2") (pintype "passive"))
      (node (ref "J2") (pin "A1B12") (pinfunction "GND_A1B12") (pintype "power_in"))
      (node (ref "J2") (pin "B1A12") (pinfunction "GND_B1A12") (pintype "power_in"))
      (node (ref "J2") (pin "S1") (pinfunction "SHIELD_S1") (pintype "passive"))
      (node (ref "J2") (pin "S2") (pinfunction "SHIELD_S2") (pintype "passive"))
      (node (ref "J2") (pin "S3") (pinfunction "SHIELD_S3") (pintype "passive"))
      (node (ref "J2") (pin "S4") (pinfunction "SHIELD_S4") (pintype "passive"))
      (node (ref "JP1") (pin "5") (pinfunction "5_5") (pintype "passive"))
      (node (ref "JP2") (pin "5") (pinfunction "5_5") (pintype "passive"))
      (node (ref "JP2") (pin "6") (pinfunction "6_6") (pintype "passive"))
      (node (ref "JP7") (pin "2") (pinfunction "2_2") (pintype "passive"))
      (node (ref "LDS_CTRL") (pin "P1") (pinfunction "1_P1") (pintype "bidirectional"))
      (node (ref "LDS_DAT") (pin "P1") (pinfunction "1_P1") (pintype "bidirectional"))
      (node (ref "LED") (pin "C") (pinfunction "C_C") (pintype "passive"))
      (node (ref "MAX4466") (pin "P1") (pinfunction "1_P1") (pintype "bidirectional"))
      (node (ref "MIX8410") (pin "1") (pinfunction "1_1") (pintype "passive"))
      (node (ref "R16") (pin "1") (pinfunction "1_1") (pintype "passive"))
      (node (ref "R21") (pin "1") (pinfunction "1_1") (pintype "passive"))
      (node (ref "R22") (pin "1") (pinfunction "1_1") (pintype "passive"))
      (node (ref "R4") (pin "2") (pinfunction "2_2") (pintype "passive"))
      (node (ref "R5") (pin "2") (pinfunction "2_2") (pintype "passive"))
      (node (ref "RESET") (pin "A") (pinfunction "A_A") (pintype "bidirectional"))
      (node (ref "RESET") (pin "B") (pinfunction "A_B") (pintype "bidirectional"))
      (node (ref "RTC1") (pin "4") (pinfunction "VSS_4") (pintype "bidirectional"))
      (node (ref "SCD30") (pin "P1") (pinfunction "1_P1") (pintype "bidirectional"))
      (node (ref "TF115") (pin "10") (pinfunction "SHIELD_10") (pintype "bidirectional"))
      (node (ref "TF115") (pin "11") (pinfunction "SHIELD_11") (pintype "bidirectional"))
      (node (ref "TF115") (pin "12") (pinfunction "SHIELD_12") (pintype "bidirectional"))
      (node (ref "TF115") (pin "13") (pinfunction "SHIELD_13") (pintype "bidirectional"))
      (node (ref "TF115") (pin "6") (pinfunction "VSS_6") (pintype "bidirectional"))
      (node (ref "TSL2591") (pin "P1") (pinfunction "1_P1") (pintype "bidirectional"))
      (node (ref "U1") (pin "21") (pinfunction "AGND_21") (pintype "bidirectional"))
      (node (ref "U1") (pin "3") (pinfunction "GND_3") (pintype "bidirectional"))
      (node (ref "U1") (pin "5") (pinfunction "GND_5") (pintype "bidirectional"))
      (node (ref "VOC_AE") (pin "P3") (pinfunction "3_P3") (pintype "bidirectional"))
      (node (ref "VOC_DAT") (pin "P1") (pinfunction "1_P1") (pintype "bidirectional"))
      (node (ref "VR1") (pin "2") (pinfunction "GND_2") (pintype "output"))
      (node (ref "VR2") (pin "1") (pinfunction "ADJ_1") (pintype "bidirectional"))
    )
    (net (code "34") (name "ISP-MI") (class "Default")
      (node (ref "JP1") (pin "4") (pinfunction "4_4") (pintype "passive"))
      (node (ref "SJ2") (pin "1") (pinfunction "1_1") (pintype "passive"))
      (node (ref "U1") (pin "16") (pinfunction "PB4(MISO)_16") (pintype "bidirectional"))
    )
    (net (code "35") (name "ISP-MO") (class "Default")
      (node (ref "JP1") (pin "2") (pinfunction "2_2") (pintype "passive"))
      (node (ref "SJ1") (pin "1") (pinfunction "1_1") (pintype "passive"))
      (node (ref "U1") (pin "15") (pinfunction "PB3(MOSI/OC2)_15") (pintype "bidirectional"))
    )
    (net (code "36") (name "ISP-SC") (class "Default")
      (node (ref "JP1") (pin "6") (pinfunction "6_6") (pintype "passive"))
      (node (ref "SJ3") (pin "1") (pinfunction "1_1") (pintype "passive"))
      (node (ref "U1") (pin "17") (pinfunction "PB5(SCK)_17") (pintype "bidirectional"))
    )
    (net (code "37") (name "LDS_RST") (class "Default")
      (node (ref "JP3") (pin "7") (pinfunction "7_7") (pintype "passive"))
      (node (ref "LDS_CTRL") (pin "P3") (pinfunction "3_P3") (pintype "bidirectional"))
      (node (ref "U1") (pin "12") (pinfunction "PB0(ICP)_12") (pintype "bidirectional"))
    )
    (net (code "38") (name "LDS_RXI") (class "Default")
      (node (ref "IC3") (pin "4") (pinfunction "Y3_4") (pintype "bidirectional"))
      (node (ref "LDS_DAT") (pin "P3") (pinfunction "3_P3") (pintype "bidirectional"))
      (node (ref "R10") (pin "1") (pinfunction "1_1") (pintype "passive"))
    )
    (net (code "39") (name "LDS_SET") (class "Default")
      (node (ref "JP3") (pin "8") (pinfunction "8_8") (pintype "passive"))
      (node (ref "LDS_CTRL") (pin "P4") (pinfunction "4_P4") (pintype "bidirectional"))
      (node (ref "U1") (pin "13") (pinfunction "PB1(OC1A)_13") (pintype "bidirectional"))
    )
    (net (code "40") (name "LDS_TXO") (class "Default")
      (node (ref "IC3") (pin "11") (pinfunction "X3_11") (pintype "bidirectional"))
      (node (ref "LDS_DAT") (pin "P4") (pinfunction "4_P4") (pintype "bidirectional"))
      (node (ref "R2") (pin "1") (pinfunction "1_1") (pintype "passive"))
    )
    (net (code "41") (name "MISO") (class "Default")
      (node (ref "JP3") (pin "11") (pinfunction "11_11") (pintype "passive"))
      (node (ref "SJ2") (pin "2") (pinfunction "2_2") (pintype "passive"))
      (node (ref "TF115") (pin "7") (pinfunction "DAT0_7") (pintype "bidirectional"))
    )
    (net (code "42") (name "MOSI") (class "Default")
      (node (ref "JP3") (pin "10") (pinfunction "10_10") (pintype "passive"))
      (node (ref "SJ1") (pin "2") (pinfunction "2_2") (pintype "passive"))
      (node (ref "TF115") (pin "3") (pinfunction "CMD_3") (pintype "bidirectional"))
    )
    (net (code "43") (name "Net-(3V3-PadA)") (class "Default")
      (node (ref "3V3") (pin "A") (pinfunction "A_A") (pintype "passive"))
      (node (ref "R11") (pin "1") (pinfunction "1_1") (pintype "passive"))
    )
    (net (code "44") (name "Net-(5V-PadA)") (class "Default")
      (node (ref "5V") (pin "A") (pinfunction "A_A") (pintype "passive"))
      (node (ref "R17") (pin "1") (pinfunction "1_1") (pintype "passive"))
    )
    (net (code "45") (name "Net-(G1-XT1)") (class "Default")
      (node (ref "C19") (pin "1") (pinfunction "1_1") (pintype "passive"))
      (node (ref "G1") (pin "P$1") (pinfunction "XT1_P$1") (pintype "bidirectional"))
      (node (ref "U1") (pin "7") (pinfunction "PB6(XTAL1/TOSC1)_7") (pintype "bidirectional"))
    )
    (net (code "46") (name "Net-(G1-XT2)") (class "Default")
      (node (ref "C20") (pin "1") (pinfunction "1_1") (pintype "passive"))
      (node (ref "G1") (pin "P$2") (pinfunction "XT2_P$2") (pintype "bidirectional"))
      (node (ref "U1") (pin "8") (pinfunction "PB7(XTAL2/TOSC2)_8") (pintype "bidirectional"))
    )
    (net (code "47") (name "Net-(IC1-REGIN)") (class "Default")
      (node (ref "C7") (pin "1") (pinfunction "1_1") (pintype "passive"))
      (node (ref "C8") (pin "1") (pinfunction "1_1") (pintype "passive"))
      (node (ref "IC1") (pin "7") (pinfunction "REGIN_7") (pintype "passive"))
      (node (ref "IC1") (pin "8") (pinfunction "VBUS_8") (pintype "input"))
      (node (ref "J2") (pin "A4B9") (pinfunction "VBUS_A4B9") (pintype "power_in"))
      (node (ref "J2") (pin "B4A9") (pinfunction "VBUS_B4A9") (pintype "power_in"))
    )
    (net (code "48") (name "Net-(IC1-VDD)") (class "Default")
      (node (ref "C5") (pin "1") (pinfunction "1_1") (pintype "passive"))
      (node (ref "C6") (pin "1") (pinfunction "1_1") (pintype "passive"))
      (node (ref "IC1") (pin "6") (pinfunction "VDD_6") (pintype "power_in"))
    )
    (net (code "49") (name "Net-(IC2-PadEN)") (class "Default")
      (node (ref "IC2") (pin "EN") (pinfunction "EN_EN") (pintype "bidirectional"))
      (node (ref "R20") (pin "1") (pinfunction "1_1") (pintype "passive"))
    )
    (net (code "50") (name "Net-(IC2-PadIO2)") (class "Default")
      (node (ref "IC2") (pin "IO2") (pinfunction "IO2_IO2") (pintype "bidirectional"))
      (node (ref "R15") (pin "2") (pinfunction "2_2") (pintype "passive"))
    )
    (net (code "51") (name "Net-(IC2-PadIO15)") (class "Default")
      (node (ref "IC2") (pin "IO15") (pinfunction "IO15_IO15") (pintype "bidirectional"))
      (node (ref "R16") (pin "2") (pinfunction "2_2") (pintype "passive"))
    )
    (net (code "52") (name "Net-(IC4-A)") (class "Default")
      (node (ref "ARD_UART") (pin "2") (pinfunction "2_2") (pintype "passive"))
      (node (ref "IC4") (pin "10") (pinfunction "A_10") (pintype "input"))
      (node (ref "R21") (pin "2") (pinfunction "2_2") (pintype "passive"))
    )
    (net (code "53") (name "Net-(IC4-B)") (class "Default")
      (node (ref "IC4") (pin "9") (pinfunction "B_9") (pintype "input"))
      (node (ref "R22") (pin "2") (pinfunction "2_2") (pintype "passive"))
    )
    (net (code "54") (name "Net-(J2-CC1)") (class "Default")
      (node (ref "J2") (pin "A5") (pinfunction "CC1_A5") (pintype "bidirectional"))
      (node (ref "R5") (pin "1") (pinfunction "1_1") (pintype "passive"))
    )
    (net (code "55") (name "Net-(J2-CC2)") (class "Default")
      (node (ref "J2") (pin "B5") (pinfunction "CC2_B5") (pintype "bidirectional"))
      (node (ref "R4") (pin "1") (pinfunction "1_1") (pintype "passive"))
    )
    (net (code "56") (name "Net-(LED-PadA)") (class "Default")
      (node (ref "LED") (pin "A") (pinfunction "A_A") (pintype "passive"))
      (node (ref "R18") (pin "2") (pinfunction "2_2") (pintype "passive"))
    )
    (net (code "57") (name "Net-(R29-Pad1)") (class "Default")
      (node (ref "R29") (pin "1") (pinfunction "1_1") (pintype "passive"))
      (node (ref "SD") (pin "A") (pinfunction "A_A") (pintype "passive"))
    )
    (net (code "58") (name "Net-(RTC1-OSCI)") (class "Default")
      (node (ref "C4") (pin "1") (pinfunction "1_1") (pintype "passive"))
      (node (ref "G2") (pin "2") (pinfunction "2_2") (pintype "bidirectional"))
      (node (ref "RTC1") (pin "1") (pinfunction "OSCI_1") (pintype "bidirectional"))
    )
    (net (code "59") (name "Net-(RTC1-OSCO)") (class "Default")
      (node (ref "C11") (pin "1") (pinfunction "1_1") (pintype "passive"))
      (node (ref "G2") (pin "1") (pinfunction "1_1") (pintype "bidirectional"))
      (node (ref "RTC1") (pin "2") (pinfunction "OSCO_2") (pintype "bidirectional"))
    )
    (net (code "60") (name "Net-(RTC1-VDD)") (class "Default")
      (node (ref "BT1") (pin "VDD") (pinfunction "VDD_VDD") (pintype "power_in"))
      (node (ref "BT1") (pin "VDD1") (pinfunction "VDD_VDD1") (pintype "power_in"))
      (node (ref "RTC1") (pin "8") (pinfunction "VDD_8") (pintype "bidirectional"))
    )
    (net (code "61") (name "Net-(VR1-VI)") (class "Default")
      (node (ref "C1") (pin "1") (pinfunction "1_1") (pintype "passive"))
      (node (ref "D2") (pin "C") (pinfunction "C_C") (pintype "passive"))
      (node (ref "VR1") (pin "1") (pinfunction "VI_1") (pintype "input"))
    )
    (net (code "62") (name "Net-(VR2-IN)") (class "Default")
      (node (ref "C10") (pin "+") (pinfunction "+_+") (pintype "passive"))
      (node (ref "D5") (pin "C") (pinfunction "C_C") (pintype "passive"))
      (node (ref "VR2") (pin "3") (pinfunction "IN_3") (pintype "input"))
    )
    (net (code "63") (name "RESET") (class "Default")
      (node (ref "C9") (pin "1") (pinfunction "1_1") (pintype "passive"))
      (node (ref "IC2") (pin "RST") (pinfunction "RST_RST") (pintype "input"))
      (node (ref "JP1") (pin "3") (pinfunction "3_3") (pintype "passive"))
      (node (ref "JP7") (pin "3") (pinfunction "3_3") (pintype "passive"))
      (node (ref "R1") (pin "2") (pinfunction "2_2") (pintype "passive"))
      (node (ref "RESET") (pin "C") (pinfunction "C_C") (pintype "bidirectional"))
      (node (ref "RESET") (pin "D") (pinfunction "C_D") (pintype "bidirectional"))
      (node (ref "U1") (pin "29") (pinfunction "PC6(/RESET)_29") (pintype "bidirectional"))
    )
    (net (code "64") (name "RTS") (class "Default")
      (node (ref "C9") (pin "2") (pinfunction "2_2") (pintype "passive"))
      (node (ref "IC1") (pin "24") (pinfunction "RTS_24") (pintype "output"))
      (node (ref "JP2") (pin "4") (pinfunction "4_4") (pintype "passive"))
    )
    (net (code "65") (name "RXI") (class "Default")
      (node (ref "IC1") (pin "26") (pinfunction "TXD_26") (pintype "output"))
      (node (ref "IC4") (pin "13") (pinfunction "X_13") (pintype "bidirectional"))
      (node (ref "JP2") (pin "3") (pinfunction "3_3") (pintype "passive"))
    )
    (net (code "66") (name "SCK") (class "Default")
      (node (ref "JP3") (pin "12") (pinfunction "12_12") (pintype "passive"))
      (node (ref "R18") (pin "1") (pinfunction "1_1") (pintype "passive"))
      (node (ref "SJ3") (pin "2") (pinfunction "2_2") (pintype "passive"))
      (node (ref "TF115") (pin "5") (pinfunction "CLK_5") (pintype "bidirectional"))
    )
    (net (code "67") (name "SCL") (class "Default")
      (node (ref "AS7262") (pin "P4") (pinfunction "4_P4") (pintype "bidirectional"))
      (node (ref "I2C_EXT") (pin "P4") (pinfunction "4_P4") (pintype "bidirectional"))
      (node (ref "JP6") (pin "1") (pinfunction "1_1") (pintype "passive"))
      (node (ref "R8") (pin "1") (pinfunction "1_1") (pintype "passive"))
      (node (ref "RTC1") (pin "6") (pinfunction "SCL_6") (pintype "bidirectional"))
      (node (ref "SCD30") (pin "P4") (pinfunction "4_P4") (pintype "bidirectional"))
      (node (ref "TSL2591") (pin "P4") (pinfunction "4_P4") (pintype "bidirectional"))
      (node (ref "U1") (pin "28") (pinfunction "PC5(ADC5/SCL)_28") (pintype "bidirectional"))
      (node (ref "VOC_DAT") (pin "P4") (pinfunction "4_P4") (pintype "bidirectional"))
    )
    (net (code "68") (name "SDA") (class "Default")
      (node (ref "AS7262") (pin "P3") (pinfunction "3_P3") (pintype "bidirectional"))
      (node (ref "I2C_EXT") (pin "P3") (pinfunction "3_P3") (pintype "bidirectional"))
      (node (ref "JP6") (pin "2") (pinfunction "2_2") (pintype "passive"))
      (node (ref "R7") (pin "1") (pinfunction "1_1") (pintype "passive"))
      (node (ref "RTC1") (pin "5") (pinfunction "SDA_5") (pintype "bidirectional"))
      (node (ref "SCD30") (pin "P3") (pinfunction "3_P3") (pintype "bidirectional"))
      (node (ref "TSL2591") (pin "P3") (pinfunction "3_P3") (pintype "bidirectional"))
      (node (ref "U1") (pin "27") (pinfunction "PC4(ADC4/SDA)_27") (pintype "bidirectional"))
      (node (ref "VOC_DAT") (pin "P3") (pinfunction "3_P3") (pintype "bidirectional"))
    )
    (net (code "69") (name "SD_CS") (class "Default")
      (node (ref "JP3") (pin "9") (pinfunction "9_9") (pintype "passive"))
      (node (ref "SD") (pin "C") (pinfunction "C_C") (pintype "passive"))
      (node (ref "TF115") (pin "2") (pinfunction "CD/DAT3_2") (pintype "bidirectional"))
      (node (ref "U1") (pin "14") (pinfunction "PB2(SS/OC1B)_14") (pintype "bidirectional"))
    )
    (net (code "70") (name "TXO") (class "Default")
      (node (ref "IC1") (pin "25") (pinfunction "RXD_25") (pintype "input"))
      (node (ref "IC4") (pin "3") (pinfunction "Y_3") (pintype "bidirectional"))
      (node (ref "JP2") (pin "2") (pinfunction "2_2") (pintype "passive"))
    )
    (net (code "71") (name "USBD+") (class "Default")
      (node (ref "IC1") (pin "4") (pinfunction "D+_4") (pintype "bidirectional"))
      (node (ref "J2") (pin "A6") (pinfunction "DP1_A6") (pintype "bidirectional"))
      (node (ref "J2") (pin "B6") (pinfunction "DP2_B6") (pintype "bidirectional"))
    )
    (net (code "72") (name "USBD-") (class "Default")
      (node (ref "IC1") (pin "5") (pinfunction "D-_5") (pintype "bidirectional"))
      (node (ref "J2") (pin "A7") (pinfunction "DN1_A7") (pintype "bidirectional"))
      (node (ref "J2") (pin "B7") (pinfunction "DN2_B7") (pintype "bidirectional"))
    )
    (net (code "73") (name "U_SEL_A") (class "Default")
      (node (ref "IC3") (pin "10") (pinfunction "A_10") (pintype "input"))
      (node (ref "JP3") (pin "5") (pinfunction "5_5") (pintype "passive"))
      (node (ref "U1") (pin "10") (pinfunction "PD6(AIN0)_10") (pintype "bidirectional"))
    )
    (net (code "74") (name "U_SEL_B") (class "Default")
      (node (ref "IC3") (pin "9") (pinfunction "B_9") (pintype "input"))
      (node (ref "JP3") (pin "4") (pinfunction "4_4") (pintype "passive"))
      (node (ref "U1") (pin "9") (pinfunction "PD5(T1)_9") (pintype "bidirectional"))
    )
    (net (code "75") (name "VIN") (class "Default")
      (node (ref "D2") (pin "A") (pinfunction "A_A") (pintype "passive"))
      (node (ref "D5") (pin "A") (pinfunction "A_A") (pintype "passive"))
      (node (ref "J1") (pin "3") (pinfunction "3_3") (pintype "passive"))
      (node (ref "JP7") (pin "1") (pinfunction "1_1") (pintype "passive"))
    )
    (net (code "76") (name "VOC_AUD") (class "Default")
      (node (ref "VOC_AE") (pin "P1") (pinfunction "1_P1") (pintype "bidirectional"))
    )
    (net (code "77") (name "VOC_EV") (class "Default")
      (node (ref "VOC_AE") (pin "P2") (pinfunction "2_P2") (pintype "bidirectional"))
    )
    (net (code "78") (name "unconnected-(IC1-CTS-Pad23)") (class "Default")
      (node (ref "IC1") (pin "23") (pinfunction "CTS_23") (pintype "input"))
    )
    (net (code "79") (name "unconnected-(IC1-DCD-Pad1)") (class "Default")
      (node (ref "IC1") (pin "1") (pinfunction "DCD_1") (pintype "input"))
    )
    (net (code "80") (name "unconnected-(IC1-DSR-Pad27)") (class "Default")
      (node (ref "IC1") (pin "27") (pinfunction "DSR_27") (pintype "input"))
    )
    (net (code "81") (name "unconnected-(IC1-RI-Pad2)") (class "Default")
      (node (ref "IC1") (pin "2") (pinfunction "RI_2") (pintype "input"))
    )
    (net (code "82") (name "unconnected-(IC1-SUSPEND-Pad12)") (class "Default")
      (node (ref "IC1") (pin "12") (pinfunction "SUSPEND_12") (pintype "output"))
    )
    (net (code "83") (name "unconnected-(IC1-~{RST}-Pad9)") (class "Default")
      (node (ref "IC1") (pin "9") (pinfunction "~{RST}_9") (pintype "bidirectional"))
    )
    (net (code "84") (name "unconnected-(IC1-~{SUSPEND}-Pad11)") (class "Default")
      (node (ref "IC1") (pin "11") (pinfunction "~{SUSPEND}_11") (pintype "output"))
    )
    (net (code "85") (name "unconnected-(IC3-X0-Pad12)") (class "Default")
      (node (ref "IC3") (pin "12") (pinfunction "X0_12") (pintype "bidirectional"))
    )
    (net (code "86") (name "unconnected-(IC3-X2-Pad15)") (class "Default")
      (node (ref "IC3") (pin "15") (pinfunction "X2_15") (pintype "bidirectional"))
    )
    (net (code "87") (name "unconnected-(IC3-Y0-Pad1)") (class "Default")
      (node (ref "IC3") (pin "1") (pinfunction "Y0_1") (pintype "bidirectional"))
    )
    (net (code "88") (name "unconnected-(IC3-Y2-Pad2)") (class "Default")
      (node (ref "IC3") (pin "2") (pinfunction "Y2_2") (pintype "bidirectional"))
    )
    (net (code "89") (name "unconnected-(IC4-X2-Pad15)") (class "Default")
      (node (ref "IC4") (pin "15") (pinfunction "X2_15") (pintype "bidirectional"))
    )
    (net (code "90") (name "unconnected-(IC4-X3-Pad11)") (class "Default")
      (node (ref "IC4") (pin "11") (pinfunction "X3_11") (pintype "bidirectional"))
    )
    (net (code "91") (name "unconnected-(IC4-Y2-Pad2)") (class "Default")
      (node (ref "IC4") (pin "2") (pinfunction "Y2_2") (pintype "bidirectional"))
    )
    (net (code "92") (name "unconnected-(IC4-Y3-Pad4)") (class "Default")
      (node (ref "IC4") (pin "4") (pinfunction "Y3_4") (pintype "bidirectional"))
    )
    (net (code "93") (name "unconnected-(J2-SBU1-PadA8)") (class "Default")
      (node (ref "J2") (pin "A8") (pinfunction "SBU1_A8") (pintype "bidirectional"))
    )
    (net (code "94") (name "unconnected-(J2-SBU2-PadB8)") (class "Default")
      (node (ref "J2") (pin "B8") (pinfunction "SBU2_B8") (pintype "bidirectional"))
    )
    (net (code "95") (name "unconnected-(MAX4466-4-PadP4)") (class "Default")
      (node (ref "MAX4466") (pin "P4") (pinfunction "4_P4") (pintype "bidirectional"))
    )
    (net (code "96") (name "unconnected-(MIX8410-Pad4)") (class "Default")
      (node (ref "MIX8410") (pin "4") (pinfunction "4_4") (pintype "passive"))
    )
    (net (code "97") (name "unconnected-(RTC1-CLKO-Pad7)") (class "Default")
      (node (ref "RTC1") (pin "7") (pinfunction "CLKO_7") (pintype "bidirectional"))
    )
    (net (code "98") (name "unconnected-(RTC1-{slash}INT-Pad3)") (class "Default")
      (node (ref "RTC1") (pin "3") (pinfunction "/INT_3") (pintype "bidirectional"))
    )
    (net (code "99") (name "unconnected-(TF115-DAT1-Pad8)") (class "Default")
      (node (ref "TF115") (pin "8") (pinfunction "DAT1_8") (pintype "bidirectional"))
    )
    (net (code "100") (name "unconnected-(TF115-DAT2-Pad1)") (class "Default")
      (node (ref "TF115") (pin "1") (pinfunction "DAT2_1") (pintype "bidirectional"))
    )
    (net (code "101") (name "unconnected-(VOC_AE-4-PadP4)") (class "Default")
      (node (ref "VOC_AE") (pin "P4") (pinfunction "4_P4") (pintype "bidirectional"))
    )
  )
)
